# Connectors-HDMI-MicroSD.net
KiCad netlist of a schematic drawn in Altium Designer
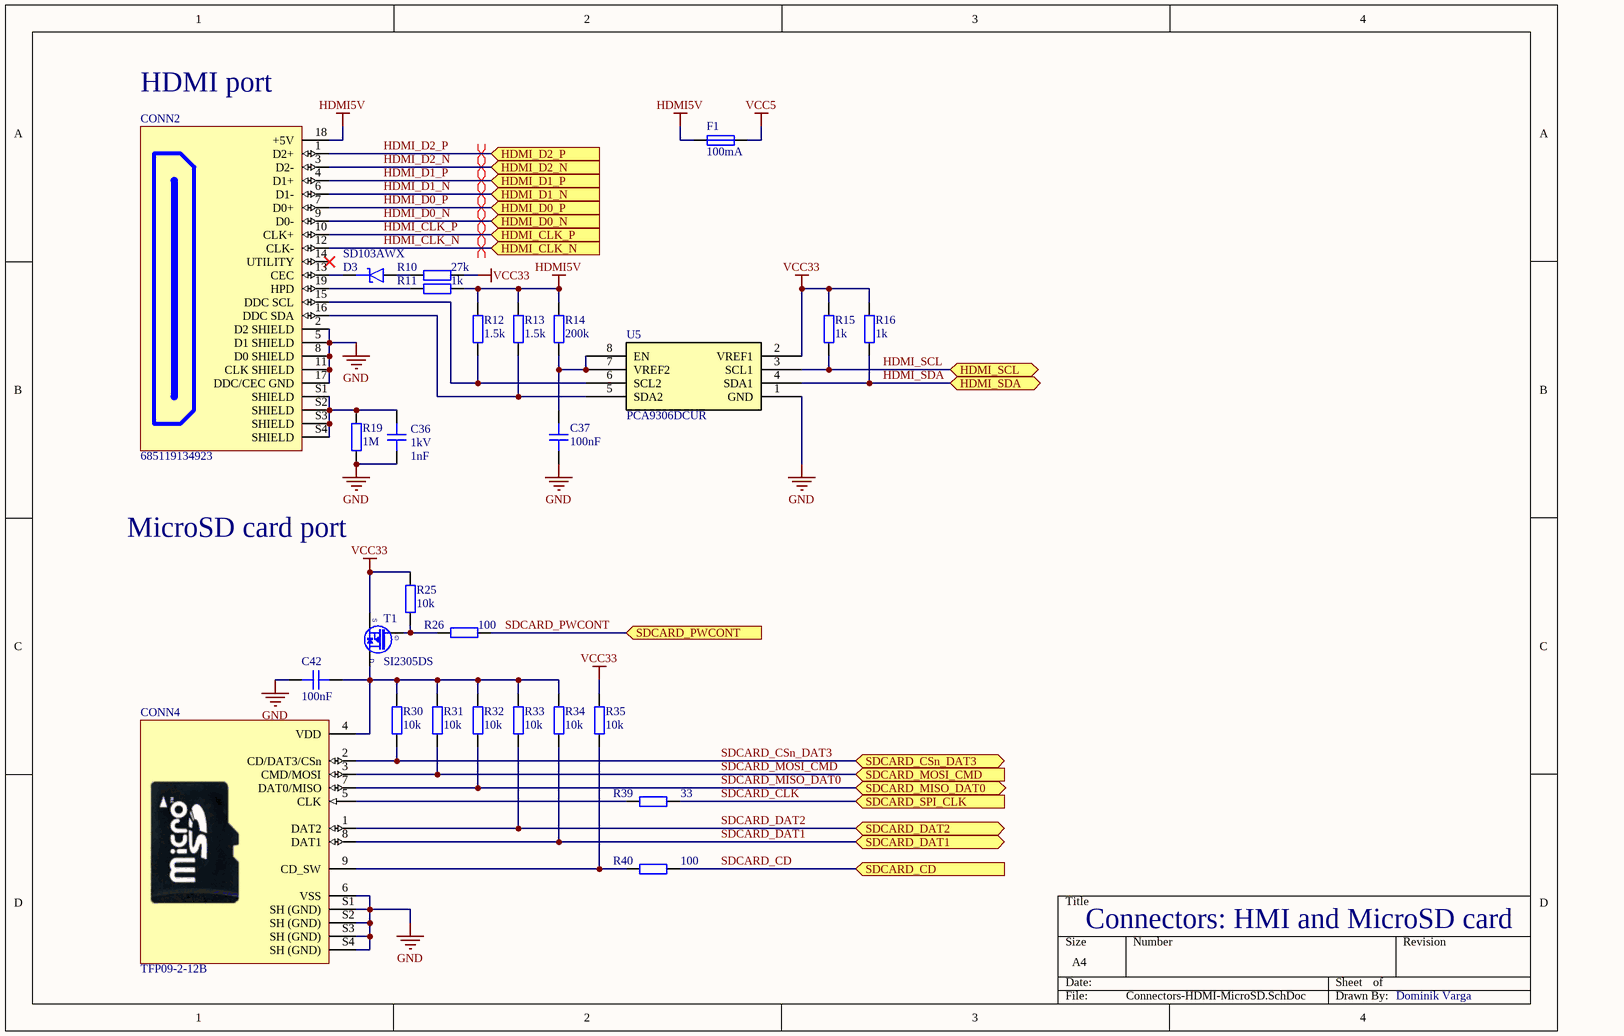
[diagram p0: Connectors-HDMI-MicroSD.SchDoc]

(export (version "E")
  (design (tool "Eeschema 10.0.6"))
  (components
    (comp (ref "C36")
      (value "1nF")
      (footprint "CAP_SMD0805")
      (description "Capacitor SMD 0805")
      (fields (field (name "VOLTAGE") "1kV"))
      (libsource (lib "NES-Components") (part "CAP_0603"))
    )
    (comp (ref "C37")
      (value "100nF")
      (footprint "CAP_SMD0603")
      (description "Capacitor SMD 0603")
      (libsource (lib "NES-Components") (part "CAP_0603"))
    )
    (comp (ref "C42")
      (value "100nF")
      (footprint "CAP_SMD0603")
      (description "Capacitor SMD 0603")
      (libsource (lib "NES-Components") (part "CAP_0603"))
    )
    (comp (ref "CONN2")
      (value "685119134923")
      (footprint "685119134923")
      (description "Würth Elektronik 685119134923 HDMI type A receptacle")
      (libsource (lib "NES-Components") (part "685119134923"))
    )
    (comp (ref "CONN4")
      (value "TFP09-2-12B")
      (footprint "TFP09-2-12B")
      (description "MicroSD card socket")
      (libsource (lib "NES-Components") (part "TFP09-2-12B"))
    )
    (comp (ref "D3")
      (value "SD103AWX")
      (footprint "SODFL1608X70N")
      (description "Schottky Barrier Diode")
      (libsource (lib "NES-Components") (part "SD103AWX"))
    )
    (comp (ref "F1")
      (value "100mA")
      (footprint "RES_SMD1206")
      (description "Fuse SMD 1206")
      (libsource (lib "NES-Components") (part "FUSE_1206"))
    )
    (comp (ref "R10")
      (value "27k")
      (footprint "RES_SMD0603")
      (description "Resistor SMD 0603")
      (libsource (lib "NES-Components") (part "RES_0603"))
    )
    (comp (ref "R11")
      (value "1k")
      (footprint "RES_SMD0603")
      (description "Resistor SMD 0603")
      (libsource (lib "NES-Components") (part "RES_0603"))
    )
    (comp (ref "R12")
      (value "1.5k")
      (footprint "RES_SMD0603")
      (description "Resistor SMD 0603")
      (libsource (lib "NES-Components") (part "RES_0603"))
    )
    (comp (ref "R13")
      (value "1.5k")
      (footprint "RES_SMD0603")
      (description "Resistor SMD 0603")
      (libsource (lib "NES-Components") (part "RES_0603"))
    )
    (comp (ref "R14")
      (value "200k")
      (footprint "RES_SMD0603")
      (description "Resistor SMD 0603")
      (libsource (lib "NES-Components") (part "RES_0603"))
    )
    (comp (ref "R15")
      (value "1k")
      (footprint "RES_SMD0603")
      (description "Resistor SMD 0603")
      (libsource (lib "NES-Components") (part "RES_0603"))
    )
    (comp (ref "R16")
      (value "1k")
      (footprint "RES_SMD0603")
      (description "Resistor SMD 0603")
      (libsource (lib "NES-Components") (part "RES_0603"))
    )
    (comp (ref "R19")
      (value "1M")
      (footprint "RES_SMD0805")
      (description "Resistor SMD 0805")
      (libsource (lib "NES-Components") (part "RES_0603"))
    )
    (comp (ref "R25")
      (value "10k")
      (footprint "RES_SMD0603")
      (description "Resistor SMD 0603")
      (libsource (lib "NES-Components") (part "RES_0603"))
    )
    (comp (ref "R26")
      (value "100")
      (footprint "RES_SMD0603")
      (description "Resistor SMD 0603")
      (libsource (lib "NES-Components") (part "RES_0603"))
    )
    (comp (ref "R30")
      (value "10k")
      (footprint "RES_SMD0603")
      (description "Resistor SMD 0603")
      (libsource (lib "NES-Components") (part "RES_0603"))
    )
    (comp (ref "R31")
      (value "10k")
      (footprint "RES_SMD0603")
      (description "Resistor SMD 0603")
      (libsource (lib "NES-Components") (part "RES_0603"))
    )
    (comp (ref "R32")
      (value "10k")
      (footprint "RES_SMD0603")
      (description "Resistor SMD 0603")
      (libsource (lib "NES-Components") (part "RES_0603"))
    )
    (comp (ref "R33")
      (value "10k")
      (footprint "RES_SMD0603")
      (description "Resistor SMD 0603")
      (libsource (lib "NES-Components") (part "RES_0603"))
    )
    (comp (ref "R34")
      (value "10k")
      (footprint "RES_SMD0603")
      (description "Resistor SMD 0603")
      (libsource (lib "NES-Components") (part "RES_0603"))
    )
    (comp (ref "R35")
      (value "10k")
      (footprint "RES_SMD0603")
      (description "Resistor SMD 0603")
      (libsource (lib "NES-Components") (part "RES_0603"))
    )
    (comp (ref "R39")
      (value "33")
      (footprint "RES_SMD0603")
      (description "Resistor SMD 0603")
      (libsource (lib "NES-Components") (part "RES_0603"))
    )
    (comp (ref "R40")
      (value "100")
      (footprint "RES_SMD0603")
      (description "Resistor SMD 0603")
      (libsource (lib "NES-Components") (part "RES_0603"))
    )
    (comp (ref "T1")
      (value "SI2305DS")
      (footprint "SOT95P240X110-3N")
      (description "P-CHANNEL MOSFET WITH DIODE SI2305DS")
      (fields
        (field (name "PART NUMBER") "BSH203")
        (field (name "MANUFACTURER") "NXP SEMICONDUCTORS")
        (field (name "AUTHOR") "CERN DEM JLC")
      )
      (libsource (lib "NES-Components") (part "P-MOSFET"))
    )
    (comp (ref "U5")
      (value "PCA9306DCUR")
      (footprint "SOP50P310X90-8N")
      (description "2-bit bidirectional 400-kHz I2C/SMBus voltage level translator 8-VSSOP -40 to 85")
      (fields (field (name "COPYRIGHT") "Copyright (C) 2023 Ultra Librarian. All rights reserved."))
      (libsource (lib "NES-Components") (part "PCA9306DCUR"))
    )
  )
  (nets
    (net (code "1") (name "/HDMI_CLK_N") (class "Default")
      (node (ref "CONN2") (pin "12") (pinfunction "CLK-_12") (pintype "bidirectional"))
    )
    (net (code "2") (name "/HDMI_CLK_P") (class "Default")
      (node (ref "CONN2") (pin "10") (pinfunction "CLK+_10") (pintype "bidirectional"))
    )
    (net (code "3") (name "/HDMI_D0_N") (class "Default")
      (node (ref "CONN2") (pin "9") (pinfunction "D0-_9") (pintype "bidirectional"))
    )
    (net (code "4") (name "/HDMI_D0_P") (class "Default")
      (node (ref "CONN2") (pin "7") (pinfunction "D0+_7") (pintype "bidirectional"))
    )
    (net (code "5") (name "/HDMI_D1_N") (class "Default")
      (node (ref "CONN2") (pin "6") (pinfunction "D1-_6") (pintype "bidirectional"))
    )
    (net (code "6") (name "/HDMI_D1_P") (class "Default")
      (node (ref "CONN2") (pin "4") (pinfunction "D1+_4") (pintype "bidirectional"))
    )
    (net (code "7") (name "/HDMI_D2_N") (class "Default")
      (node (ref "CONN2") (pin "3") (pinfunction "D2-_3") (pintype "bidirectional"))
    )
    (net (code "8") (name "/HDMI_D2_P") (class "Default")
      (node (ref "CONN2") (pin "1") (pinfunction "D2+_1") (pintype "bidirectional"))
    )
    (net (code "9") (name "/HDMI_SCL") (class "Default")
      (node (ref "R15") (pin "1") (pinfunction "1_1") (pintype "passive"))
      (node (ref "U5") (pin "3") (pinfunction "SCL1_3") (pintype "passive"))
    )
    (net (code "10") (name "/HDMI_SDA") (class "Default")
      (node (ref "R16") (pin "1") (pinfunction "1_1") (pintype "passive"))
      (node (ref "U5") (pin "4") (pinfunction "SDA1_4") (pintype "passive"))
    )
    (net (code "11") (name "/SDCARD_CD") (class "Default")
      (node (ref "R40") (pin "1") (pinfunction "1_1") (pintype "passive"))
    )
    (net (code "12") (name "/SDCARD_CLK") (class "Default")
      (node (ref "R39") (pin "1") (pinfunction "1_1") (pintype "passive"))
    )
    (net (code "13") (name "/SDCARD_CSn_DAT3") (class "Default")
      (node (ref "CONN4") (pin "2") (pinfunction "CD/DAT3/CSn_2") (pintype "bidirectional"))
      (node (ref "R30") (pin "2") (pinfunction "2_2") (pintype "passive"))
    )
    (net (code "14") (name "/SDCARD_DAT1") (class "Default")
      (node (ref "CONN4") (pin "8") (pinfunction "DAT1_8") (pintype "bidirectional"))
      (node (ref "R34") (pin "2") (pinfunction "2_2") (pintype "passive"))
    )
    (net (code "15") (name "/SDCARD_DAT2") (class "Default")
      (node (ref "CONN4") (pin "1") (pinfunction "DAT2_1") (pintype "bidirectional"))
      (node (ref "R33") (pin "2") (pinfunction "2_2") (pintype "passive"))
    )
    (net (code "16") (name "/SDCARD_MISO_DAT0") (class "Default")
      (node (ref "CONN4") (pin "7") (pinfunction "DAT0/MISO_7") (pintype "bidirectional"))
      (node (ref "R32") (pin "2") (pinfunction "2_2") (pintype "passive"))
    )
    (net (code "17") (name "/SDCARD_MOSI_CMD") (class "Default")
      (node (ref "CONN4") (pin "3") (pinfunction "CMD/MOSI_3") (pintype "bidirectional"))
      (node (ref "R31") (pin "2") (pinfunction "2_2") (pintype "passive"))
    )
    (net (code "18") (name "/SDCARD_PWCONT") (class "Default")
      (node (ref "R26") (pin "1") (pinfunction "1_1") (pintype "passive"))
    )
    (net (code "19") (name "GND") (class "Default")
      (node (ref "C36") (pin "1") (pinfunction "1_1") (pintype "passive"))
      (node (ref "C37") (pin "1") (pinfunction "1_1") (pintype "passive"))
      (node (ref "C42") (pin "2") (pinfunction "2_2") (pintype "passive"))
      (node (ref "CONN2") (pin "11") (pinfunction "CLK_SHIELD_11") (pintype "passive"))
      (node (ref "CONN2") (pin "17") (pinfunction "DDC/CEC_GND_17") (pintype "passive"))
      (node (ref "CONN2") (pin "2") (pinfunction "D2_SHIELD_2") (pintype "passive"))
      (node (ref "CONN2") (pin "5") (pinfunction "D1_SHIELD_5") (pintype "passive"))
      (node (ref "CONN2") (pin "8") (pinfunction "D0_SHIELD_8") (pintype "passive"))
      (node (ref "CONN4") (pin "6") (pinfunction "VSS_6") (pintype "power_in"))
      (node (ref "CONN4") (pin "S1") (pinfunction "SH_(GND)_S1") (pintype "passive"))
      (node (ref "CONN4") (pin "S2") (pinfunction "SH_(GND)_S2") (pintype "passive"))
      (node (ref "CONN4") (pin "S3") (pinfunction "SH_(GND)_S3") (pintype "passive"))
      (node (ref "CONN4") (pin "S4") (pinfunction "SH_(GND)_S4") (pintype "passive"))
      (node (ref "R19") (pin "1") (pinfunction "1_1") (pintype "passive"))
      (node (ref "U5") (pin "1") (pinfunction "GND_1") (pintype "power_in"))
    )
    (net (code "20") (name "HDMI5V") (class "Default")
      (node (ref "CONN2") (pin "18") (pinfunction "+5V_18") (pintype "passive"))
      (node (ref "F1") (pin "1") (pinfunction "1_1") (pintype "passive"))
      (node (ref "R11") (pin "1") (pinfunction "1_1") (pintype "passive"))
      (node (ref "R12") (pin "2") (pinfunction "2_2") (pintype "passive"))
      (node (ref "R13") (pin "2") (pinfunction "2_2") (pintype "passive"))
      (node (ref "R14") (pin "2") (pinfunction "2_2") (pintype "passive"))
    )
    (net (code "21") (name "Net-(C36-Pad2)") (class "Default")
      (node (ref "C36") (pin "2") (pinfunction "2_2") (pintype "passive"))
      (node (ref "CONN2") (pin "S1") (pinfunction "SHIELD_S1") (pintype "passive"))
      (node (ref "CONN2") (pin "S2") (pinfunction "SHIELD_S2") (pintype "passive"))
      (node (ref "CONN2") (pin "S3") (pinfunction "SHIELD_S3") (pintype "passive"))
      (node (ref "CONN2") (pin "S4") (pinfunction "SHIELD_S4") (pintype "passive"))
      (node (ref "R19") (pin "2") (pinfunction "2_2") (pintype "passive"))
    )
    (net (code "22") (name "Net-(CONN2-CEC)") (class "Default")
      (node (ref "CONN2") (pin "13") (pinfunction "CEC_13") (pintype "bidirectional"))
      (node (ref "D3") (pin "1") (pinfunction "K_1") (pintype "passive"))
    )
    (net (code "23") (name "Net-(CONN2-DDC_SCL)") (class "Default")
      (node (ref "CONN2") (pin "15") (pinfunction "DDC_SCL_15") (pintype "bidirectional"))
      (node (ref "R12") (pin "1") (pinfunction "1_1") (pintype "passive"))
      (node (ref "U5") (pin "6") (pinfunction "SCL2_6") (pintype "passive"))
    )
    (net (code "24") (name "Net-(CONN2-DDC_SDA)") (class "Default")
      (node (ref "CONN2") (pin "16") (pinfunction "DDC_SDA_16") (pintype "bidirectional"))
      (node (ref "R13") (pin "1") (pinfunction "1_1") (pintype "passive"))
      (node (ref "U5") (pin "5") (pinfunction "SDA2_5") (pintype "passive"))
    )
    (net (code "25") (name "Net-(CONN2-HPD)") (class "Default")
      (node (ref "CONN2") (pin "19") (pinfunction "HPD_19") (pintype "bidirectional"))
      (node (ref "R11") (pin "2") (pinfunction "2_2") (pintype "passive"))
    )
    (net (code "26") (name "Net-(CONN4-CD_SW)") (class "Default")
      (node (ref "CONN4") (pin "9") (pinfunction "CD_SW_9") (pintype "passive"))
      (node (ref "R35") (pin "2") (pinfunction "2_2") (pintype "passive"))
      (node (ref "R40") (pin "2") (pinfunction "2_2") (pintype "passive"))
    )
    (net (code "27") (name "Net-(CONN4-CLK)") (class "Default")
      (node (ref "CONN4") (pin "5") (pinfunction "CLK_5") (pintype "input"))
      (node (ref "R39") (pin "2") (pinfunction "2_2") (pintype "passive"))
    )
    (net (code "28") (name "Net-(CONN4-VDD)") (class "Default")
      (node (ref "C42") (pin "1") (pinfunction "1_1") (pintype "passive"))
      (node (ref "CONN4") (pin "4") (pinfunction "VDD_4") (pintype "power_in"))
      (node (ref "R30") (pin "1") (pinfunction "1_1") (pintype "passive"))
      (node (ref "R31") (pin "1") (pinfunction "1_1") (pintype "passive"))
      (node (ref "R32") (pin "1") (pinfunction "1_1") (pintype "passive"))
      (node (ref "R33") (pin "1") (pinfunction "1_1") (pintype "passive"))
      (node (ref "R34") (pin "1") (pinfunction "1_1") (pintype "passive"))
      (node (ref "T1") (pin "3") (pinfunction "D_3") (pintype "passive"))
    )
    (net (code "29") (name "Net-(D3-A)") (class "Default")
      (node (ref "D3") (pin "2") (pinfunction "A_2") (pintype "passive"))
      (node (ref "R10") (pin "2") (pinfunction "2_2") (pintype "passive"))
    )
    (net (code "30") (name "Net-(T1-G)") (class "Default")
      (node (ref "R25") (pin "2") (pinfunction "2_2") (pintype "passive"))
      (node (ref "R26") (pin "2") (pinfunction "2_2") (pintype "passive"))
      (node (ref "T1") (pin "1") (pinfunction "G_1") (pintype "passive"))
    )
    (net (code "31") (name "Net-(U5-EN)") (class "Default")
      (node (ref "C37") (pin "2") (pinfunction "2_2") (pintype "passive"))
      (node (ref "R14") (pin "1") (pinfunction "1_1") (pintype "passive"))
      (node (ref "U5") (pin "7") (pinfunction "VREF2_7") (pintype "power_in"))
      (node (ref "U5") (pin "8") (pinfunction "EN_8") (pintype "passive"))
    )
    (net (code "32") (name "VCC5") (class "Default")
      (node (ref "F1") (pin "2") (pinfunction "2_2") (pintype "passive"))
    )
    (net (code "33") (name "VCC33") (class "Default")
      (node (ref "R10") (pin "1") (pinfunction "1_1") (pintype "passive"))
      (node (ref "R15") (pin "2") (pinfunction "2_2") (pintype "passive"))
      (node (ref "R16") (pin "2") (pinfunction "2_2") (pintype "passive"))
      (node (ref "R25") (pin "1") (pinfunction "1_1") (pintype "passive"))
      (node (ref "R35") (pin "1") (pinfunction "1_1") (pintype "passive"))
      (node (ref "T1") (pin "2") (pinfunction "S_2") (pintype "passive"))
      (node (ref "U5") (pin "2") (pinfunction "VREF1_2") (pintype "power_in"))
    )
    (net (code "34") (name "unconnected-(CONN2-UTILITY-Pad14)") (class "Default")
      (node (ref "CONN2") (pin "14") (pinfunction "UTILITY_14") (pintype "bidirectional+no_connect"))
    )
  )
)
